# schematic.net
KiCad netlist of a schematic drawn in Altium Designer
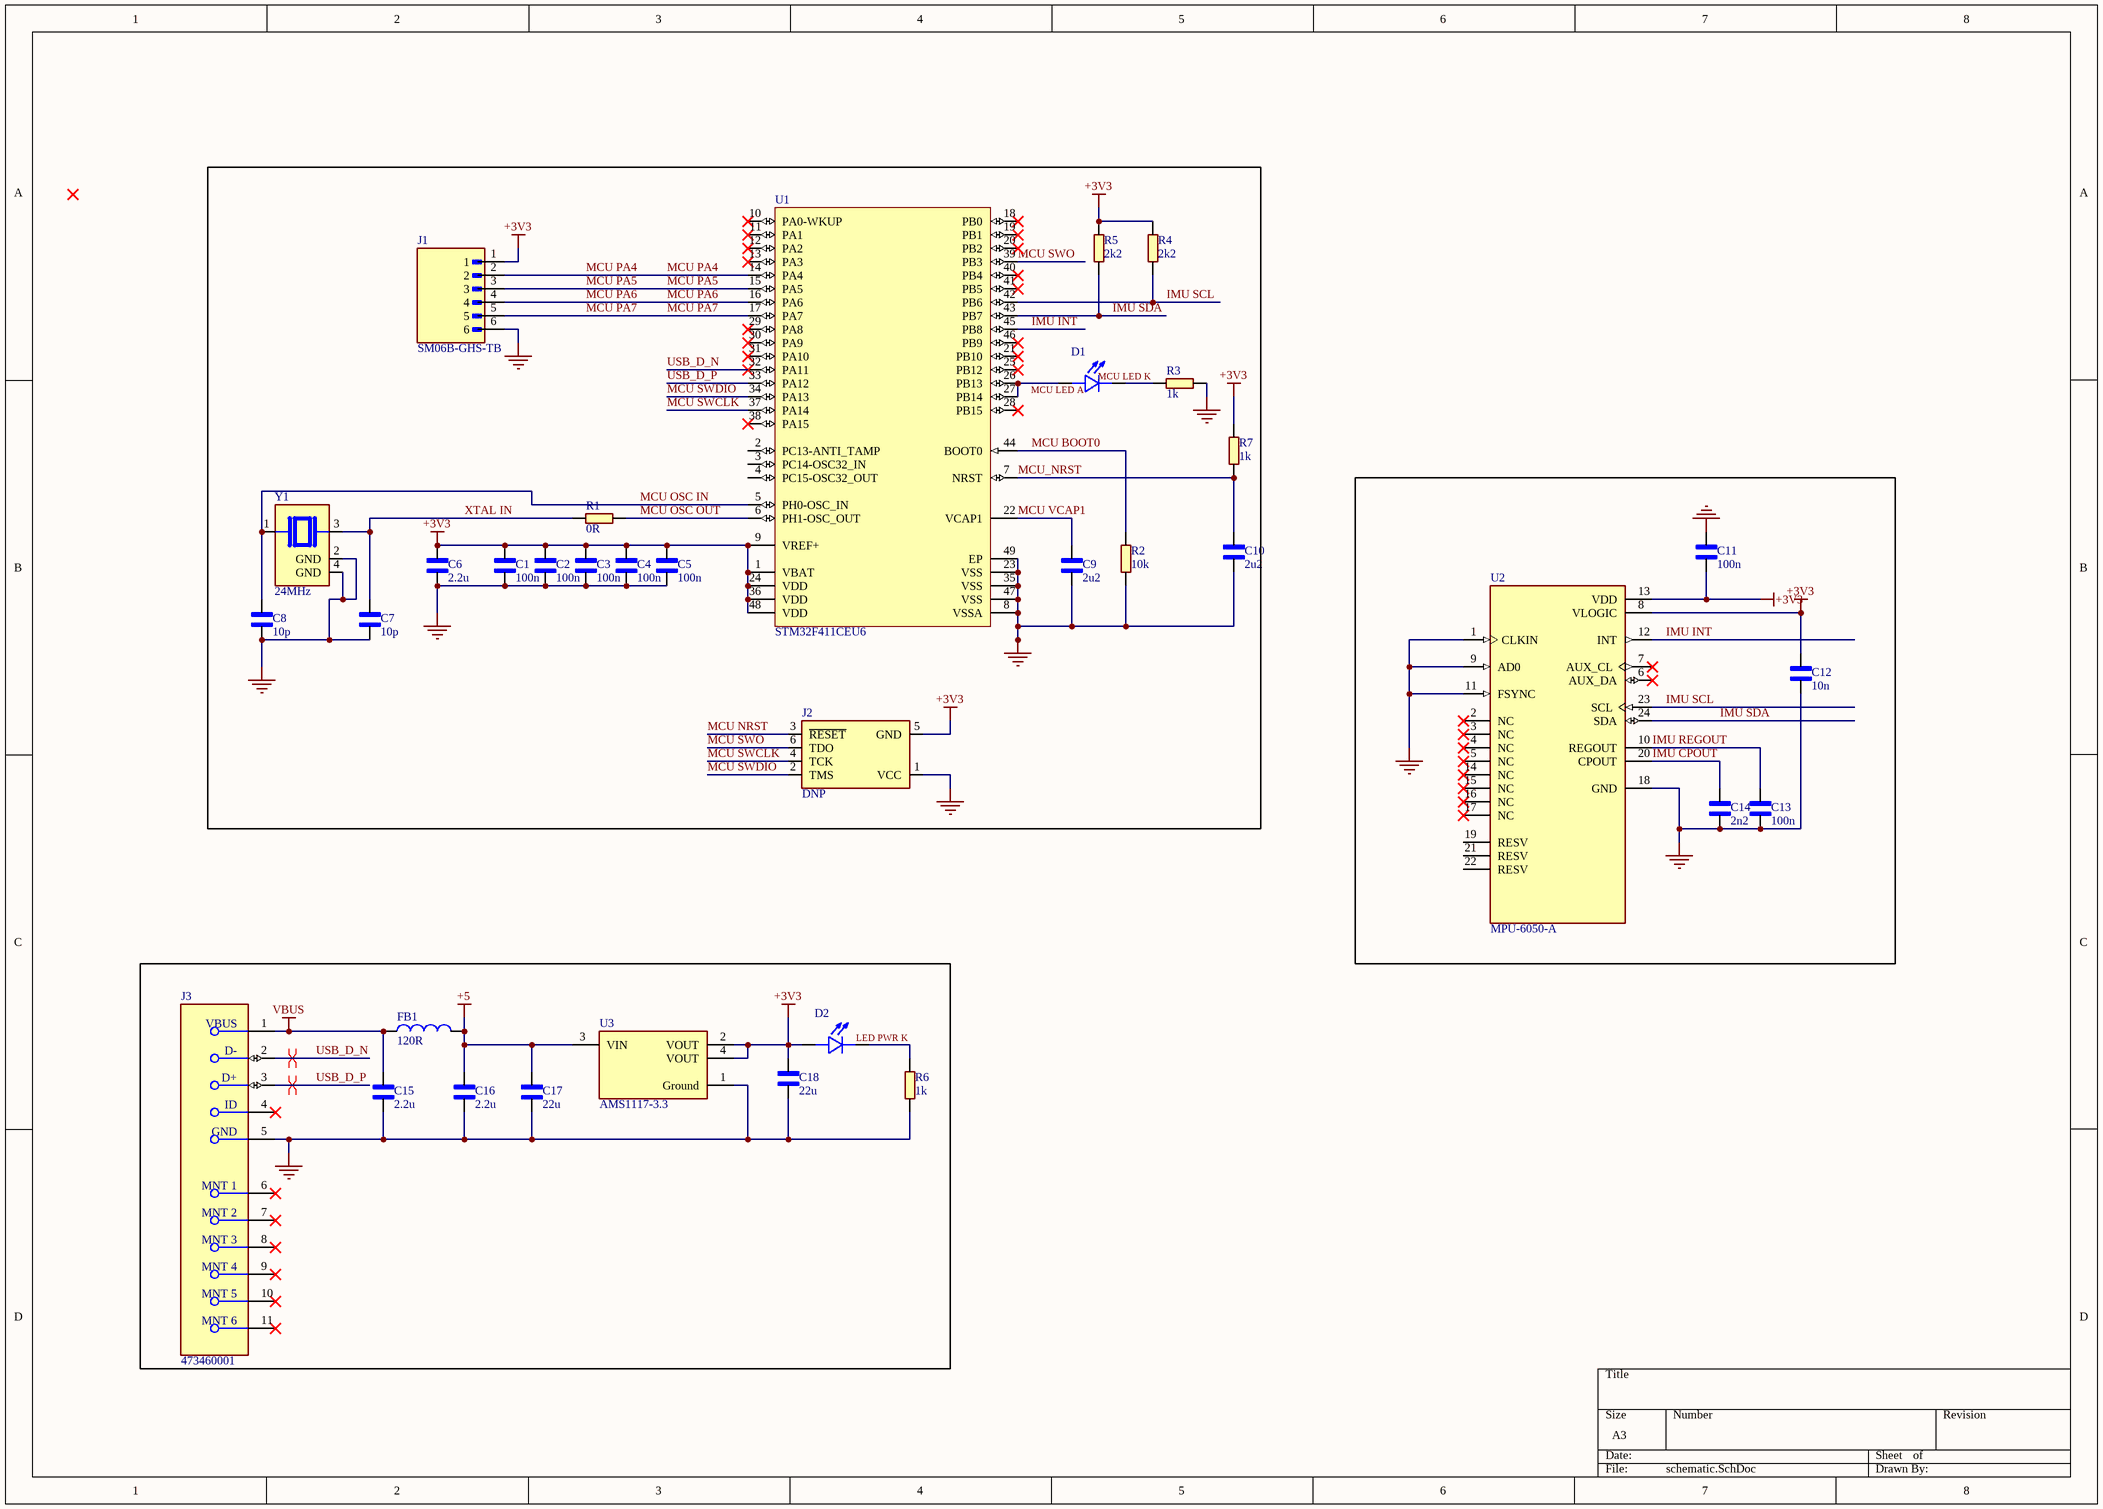
[diagram p0: schematic.SchDoc]

(export (version "E")
  (design (tool "Eeschema 10.0.6"))
  (components
    (comp (ref "C1")
      (value "100n")
      (footprint "CAPC1005X55N")
      (description "10000 pF Â±10% 16V Ceramic Capacitor X7R 0402 (1005 Metric)")
      (fields (field (name "MF") "KEMET") (field (name "MP") "C0402C103K4RAC"))
      (libsource (lib "C0402C103K4RAC") (part "C0402C103K4RAC"))
    )
    (comp (ref "C2")
      (value "100n")
      (footprint "CAPC1005X55N")
      (description "10000 pF Â±10% 16V Ceramic Capacitor X7R 0402 (1005 Metric)")
      (fields (field (name "MF") "KEMET") (field (name "MP") "C0402C103K4RAC"))
      (libsource (lib "C0402C103K4RAC") (part "C0402C103K4RAC"))
    )
    (comp (ref "C3")
      (value "100n")
      (footprint "CAPC1005X55N")
      (description "10000 pF Â±10% 16V Ceramic Capacitor X7R 0402 (1005 Metric)")
      (fields (field (name "MF") "KEMET") (field (name "MP") "C0402C103K4RAC"))
      (libsource (lib "C0402C103K4RAC") (part "C0402C103K4RAC"))
    )
    (comp (ref "C4")
      (value "100n")
      (footprint "CAPC1005X55N")
      (description "10000 pF Â±10% 16V Ceramic Capacitor X7R 0402 (1005 Metric)")
      (fields (field (name "MF") "KEMET") (field (name "MP") "C0402C103K4RAC"))
      (libsource (lib "C0402C103K4RAC") (part "C0402C103K4RAC"))
    )
    (comp (ref "C5")
      (value "100n")
      (footprint "CAPC1005X55N")
      (description "10000 pF Â±10% 16V Ceramic Capacitor X7R 0402 (1005 Metric)")
      (fields (field (name "MF") "KEMET") (field (name "MP") "C0402C103K4RAC"))
      (libsource (lib "C0402C103K4RAC") (part "C0402C103K4RAC"))
    )
    (comp (ref "C6")
      (value "2.2u")
      (footprint "CAPC1608X90N")
      (description "0.1 ÂµF Â±5% 16V Ceramic Capacitor X7R 0603 (1608 Metric)")
      (fields (field (name "MF") "KEMET") (field (name "MP") "C0603C104J4RAC"))
      (libsource (lib "C0603C104J4RAC") (part "C0603C104J4RAC"))
    )
    (comp (ref "C7")
      (value "10p")
      (footprint "CAPC1005X55N")
      (description "10000 pF Â±10% 16V Ceramic Capacitor X7R 0402 (1005 Metric)")
      (fields (field (name "MF") "KEMET") (field (name "MP") "C0402C103K4RAC"))
      (libsource (lib "C0402C103K4RAC") (part "C0402C103K4RAC"))
    )
    (comp (ref "C8")
      (value "10p")
      (footprint "CAPC1005X55N")
      (description "10000 pF Â±10% 16V Ceramic Capacitor X7R 0402 (1005 Metric)")
      (fields (field (name "MF") "KEMET") (field (name "MP") "C0402C103K4RAC"))
      (libsource (lib "C0402C103K4RAC") (part "C0402C103K4RAC"))
    )
    (comp (ref "C9")
      (value "2u2")
      (footprint "CAPC1608X90N")
      (description "0.1 ÂµF Â±5% 16V Ceramic Capacitor X7R 0603 (1608 Metric)")
      (fields (field (name "MF") "KEMET") (field (name "MP") "C0603C104J4RAC"))
      (libsource (lib "C0603C104J4RAC") (part "C0603C104J4RAC"))
    )
    (comp (ref "C10")
      (value "2u2")
      (footprint "CAPC1005X55N")
      (description "10000 pF Â±10% 16V Ceramic Capacitor X7R 0402 (1005 Metric)")
      (fields (field (name "MF") "KEMET") (field (name "MP") "C0402C103K4RAC"))
      (libsource (lib "C0402C103K4RAC") (part "C0402C103K4RAC"))
    )
    (comp (ref "C11")
      (value "100n")
      (footprint "CAPC1005X55N")
      (description "10000 pF Â±10% 16V Ceramic Capacitor X7R 0402 (1005 Metric)")
      (fields (field (name "MF") "KEMET") (field (name "MP") "C0402C103K4RAC"))
      (libsource (lib "C0402C103K4RAC") (part "C0402C103K4RAC"))
    )
    (comp (ref "C12")
      (value "10n")
      (footprint "CAPC1005X55N")
      (description "10000 pF Â±10% 16V Ceramic Capacitor X7R 0402 (1005 Metric)")
      (fields (field (name "MF") "KEMET") (field (name "MP") "C0402C103K4RAC"))
      (libsource (lib "C0402C103K4RAC") (part "C0402C103K4RAC"))
    )
    (comp (ref "C13")
      (value "100n")
      (footprint "CAPC1005X55N")
      (description "10000 pF Â±10% 16V Ceramic Capacitor X7R 0402 (1005 Metric)")
      (fields (field (name "MF") "KEMET") (field (name "MP") "C0402C103K4RAC"))
      (libsource (lib "C0402C103K4RAC") (part "C0402C103K4RAC"))
    )
    (comp (ref "C14")
      (value "2n2")
      (footprint "CAPC1005X55N")
      (description "10000 pF Â±10% 16V Ceramic Capacitor X7R 0402 (1005 Metric)")
      (fields (field (name "MF") "KEMET") (field (name "MP") "C0402C103K4RAC"))
      (libsource (lib "C0402C103K4RAC") (part "C0402C103K4RAC"))
    )
    (comp (ref "C15")
      (value "2.2u")
      (footprint "CAPC1608X90N")
      (description "0.1 ÂµF Â±5% 16V Ceramic Capacitor X7R 0603 (1608 Metric)")
      (fields (field (name "MF") "KEMET") (field (name "MP") "C0603C104J4RAC"))
      (libsource (lib "C0603C104J4RAC") (part "C0603C104J4RAC"))
    )
    (comp (ref "C16")
      (value "2.2u")
      (footprint "CAPC1608X90N")
      (description "0.1 ÂµF Â±5% 16V Ceramic Capacitor X7R 0603 (1608 Metric)")
      (fields (field (name "MF") "KEMET") (field (name "MP") "C0603C104J4RAC"))
      (libsource (lib "C0603C104J4RAC") (part "C0603C104J4RAC"))
    )
    (comp (ref "C17")
      (value "22u")
      (footprint "CAPC1608X90N")
      (description "0.1 ÂµF Â±5% 16V Ceramic Capacitor X7R 0603 (1608 Metric)")
      (fields (field (name "MF") "KEMET") (field (name "MP") "C0603C104J4RAC"))
      (libsource (lib "C0603C104J4RAC") (part "C0603C104J4RAC"))
    )
    (comp (ref "C18")
      (value "22u")
      (footprint "CAPC1608X90N")
      (description "0.1 ÂµF Â±5% 16V Ceramic Capacitor X7R 0603 (1608 Metric)")
      (fields (field (name "MF") "KEMET") (field (name "MP") "C0603C104J4RAC"))
      (libsource (lib "C0603C104J4RAC") (part "C0603C104J4RAC"))
    )
    (comp (ref "D1")
      (value "APHHS1005LSECK/J3-PF")
      (footprint "LED_APHHS1005LSECK/J3-PF")
      (description "Red 625nm LED Indication - Discrete 1.8V 0402 (1005 Metric)")
      (fields (field (name "MF") "Kingbright"))
      (libsource (lib "APHHS1005LSECK_J3-PF") (part "APHHS1005LSECK/J3-PF"))
    )
    (comp (ref "D2")
      (value "APHHS1005LCGCK")
      (footprint "LED_APHHS1005LCGCK")
      (description "Green 570nm LED Indication - Discrete 1.9V 0402 (1005 Metric)")
      (fields (field (name "MF") "Kingbright"))
      (libsource (lib "APHHS1005LCGCK") (part "APHHS1005LCGCK"))
    )
    (comp (ref "FB1")
      (value "120R")
      (footprint "WE-PF_1280")
      (description "FERRITE BEAD 185 OHM 2SMD 1LN")
      (fields (field (name "MF") "WÃ¼rth Elektronik") (field (name "MP") "7427929115"))
      (libsource (lib "WE-PF_1280") (part "WE-PF_1280"))
    )
    (comp (ref "J1")
      (value "SM06B-GHS-TB")
      (footprint "JST_SM06B-GHS-TB")
      (description "Connector Header Surface Mount, Right Angle 6 position 0.049 (1.25mm)")
      (fields (field (name "MF") "JST Sales"))
      (libsource (lib "SM06B-GHS-TB") (part "SM06B-GHS-TB"))
    )
    (comp (ref "J2")
      (value "DNP")
      (footprint "TC2030-IDC-NL")
      (description "CortexÂ® Plug-Of-Nailsâ„¢ Adapter Cable")
      (fields (field (name "MP") "TC2030-CTX") (field (name "MF") "Tag-Connect LLC"))
      (libsource (lib "TC2030-CTX") (part "TC2030-CTX"))
    )
    (comp (ref "J3")
      (value "473460001")
      (footprint "FP-473460001-MFG")
      (description "CONN RCPT USB2.0 MICRO B SMD R/A")
      (fields
        (field (name "OCTOPART") "https://octopart.com/47346-0001-molex-7164928")
        (field (name "MANUFACTURER") "Molex")
      )
      (libsource (lib "Altium Content Vault") (part "53ae1f1d9b557310b43ca686e5bb76a"))
    )
    (comp (ref "R1")
      (value "0R")
      (footprint "0402")
      (description "Reducer,NEMA 1,4 X 2 1/2 ¦ Wiegmann R0402")
      (fields (field (name "MF") "Wiegmann") (field (name "MP") "R0402"))
      (libsource (lib "") (part "R0402_1"))
    )
    (comp (ref "R2")
      (value "10k")
      (footprint "0402")
      (description "Reducer,NEMA 1,4 X 2 1/2 ¦ Wiegmann R0402")
      (fields (field (name "MF") "Wiegmann") (field (name "MP") "R0402"))
      (libsource (lib "R0402") (part "R0402"))
    )
    (comp (ref "R3")
      (value "1k")
      (footprint "0402")
      (description "Reducer,NEMA 1,4 X 2 1/2 ¦ Wiegmann R0402")
      (fields (field (name "MF") "Wiegmann") (field (name "MP") "R0402"))
      (libsource (lib "") (part "R0402_3"))
    )
    (comp (ref "R4")
      (value "2k2")
      (footprint "0402")
      (description "Reducer,NEMA 1,4 X 2 1/2 ¦ Wiegmann R0402")
      (fields (field (name "MF") "Wiegmann") (field (name "MP") "R0402"))
      (libsource (lib "R0402") (part "R0402"))
    )
    (comp (ref "R5")
      (value "2k2")
      (footprint "0402")
      (description "Reducer,NEMA 1,4 X 2 1/2 ¦ Wiegmann R0402")
      (fields (field (name "MF") "Wiegmann") (field (name "MP") "R0402"))
      (libsource (lib "R0402") (part "R0402"))
    )
    (comp (ref "R6")
      (value "1k")
      (footprint "0402")
      (description "Reducer,NEMA 1,4 X 2 1/2 ¦ Wiegmann R0402")
      (fields (field (name "MF") "Wiegmann") (field (name "MP") "R0402"))
      (libsource (lib "R0402") (part "R0402"))
    )
    (comp (ref "R7")
      (value "1k")
      (footprint "0402")
      (description "Reducer,NEMA 1,4 X 2 1/2 ¦ Wiegmann R0402")
      (fields (field (name "MF") "Wiegmann") (field (name "MP") "R0402"))
      (libsource (lib "") (part "R0402_2"))
    )
    (comp (ref "U1")
      (value "STM32F411CEU6")
      (footprint "STM-UFQFPN48_L")
      (libsource (lib "Altium Content Vault") (part "MC-ARM-STM32F411-UFQFPN48"))
    )
    (comp (ref "U2")
      (value "MPU-6050-A")
      (footprint "QFN50P400X400X95-24N")
      (fields (field (name "MF") "TDK InvenSense"))
      (libsource (lib "MPU-6050-A") (part "MPU-6050-A"))
    )
    (comp (ref "U3")
      (value "AMS1117-3.3")
      (footprint "FP-AMS1117-IPC_C")
      (description "LDO Voltage Regulators 1A, 3.3V")
      (fields
        (field (name "OCTOPART") "https://octopart.com/ams1117-3.3-advanced+monolithic+systems-25899300")
        (field (name "MANUFACTURER") "Advanced Monolithic Systems")
      )
      (libsource (lib "Altium Content Vault") (part "8bdbb5f8e77002000e30dd2845d0354"))
    )
    (comp (ref "Y1")
      (value "24MHz")
      (footprint "XTAL_TSX-3225_24.0000MF15V-C0")
      (description "24 MHz Â±10ppm Crystal 18pF 40 Ohms 4-SMD, No Lead")
      (fields (field (name "MF") "EPSON") (field (name "DIGI-KEY_PART_NUMBER") "SER4209TR-ND"))
      (libsource (lib "TSX-3225_24.0000MF15V-C0") (part "TSX-3225_24.0000MF15V-C0"))
    )
  )
  (nets
    (net (code "1") (name "+3V3") (class "Default")
      (node (ref "C1") (pin "2") (pinfunction "2_2") (pintype "passive"))
      (node (ref "C11") (pin "1") (pinfunction "1_1") (pintype "passive"))
      (node (ref "C12") (pin "2") (pinfunction "2_2") (pintype "passive"))
      (node (ref "C18") (pin "2") (pinfunction "2_2") (pintype "passive"))
      (node (ref "C2") (pin "2") (pinfunction "2_2") (pintype "passive"))
      (node (ref "C3") (pin "2") (pinfunction "2_2") (pintype "passive"))
      (node (ref "C4") (pin "2") (pinfunction "2_2") (pintype "passive"))
      (node (ref "C5") (pin "2") (pinfunction "2_2") (pintype "passive"))
      (node (ref "C6") (pin "2") (pinfunction "2_2") (pintype "passive"))
      (node (ref "D2") (pin "2") (pinfunction "A_2") (pintype "passive"))
      (node (ref "J1") (pin "1") (pinfunction "1_1") (pintype "passive"))
      (node (ref "J2") (pin "5") (pinfunction "GND_5") (pintype "bidirectional"))
      (node (ref "R4") (pin "2") (pinfunction "2_2") (pintype "passive"))
      (node (ref "R5") (pin "2") (pinfunction "2_2") (pintype "passive"))
      (node (ref "R7") (pin "1") (pinfunction "1_1") (pintype "passive"))
      (node (ref "U1") (pin "1") (pinfunction "VBAT_1") (pintype "power_in"))
      (node (ref "U1") (pin "24") (pinfunction "VDD_24") (pintype "power_in"))
      (node (ref "U1") (pin "36") (pinfunction "VDD_36") (pintype "power_in"))
      (node (ref "U1") (pin "48") (pinfunction "VDD_48") (pintype "power_in"))
      (node (ref "U1") (pin "9") (pinfunction "VREF+_9") (pintype "power_in"))
      (node (ref "U2") (pin "13") (pinfunction "VDD_13") (pintype "power_in"))
      (node (ref "U2") (pin "8") (pinfunction "VLOGIC_8") (pintype "power_in"))
      (node (ref "U3") (pin "2") (pinfunction "VOUT_2") (pintype "passive"))
      (node (ref "U3") (pin "4") (pinfunction "VOUT_4") (pintype "passive"))
    )
    (net (code "2") (name "+5") (class "Default")
      (node (ref "C16") (pin "2") (pinfunction "2_2") (pintype "passive"))
      (node (ref "C17") (pin "2") (pinfunction "2_2") (pintype "passive"))
      (node (ref "FB1") (pin "2") (pinfunction "2_2") (pintype "passive"))
      (node (ref "U3") (pin "3") (pinfunction "VIN_3") (pintype "power_in"))
    )
    (net (code "3") (name "/IMU CPOUT") (class "Default")
      (node (ref "C14") (pin "2") (pinfunction "2_2") (pintype "passive"))
      (node (ref "U2") (pin "20") (pinfunction "CPOUT_20") (pintype "passive"))
    )
    (net (code "4") (name "/IMU INT") (class "Default")
      (node (ref "U1") (pin "45") (pinfunction "PB8_45") (pintype "bidirectional"))
      (node (ref "U2") (pin "12") (pinfunction "INT_12") (pintype "output"))
    )
    (net (code "5") (name "/IMU REGOUT") (class "Default")
      (node (ref "C13") (pin "2") (pinfunction "2_2") (pintype "passive"))
      (node (ref "U2") (pin "10") (pinfunction "REGOUT_10") (pintype "passive"))
    )
    (net (code "6") (name "/IMU SCL") (class "Default")
      (node (ref "R4") (pin "1") (pinfunction "1_1") (pintype "passive"))
      (node (ref "U1") (pin "42") (pinfunction "PB6_42") (pintype "bidirectional"))
      (node (ref "U2") (pin "23") (pinfunction "SCL_23") (pintype "input"))
    )
    (net (code "7") (name "/IMU SDA") (class "Default")
      (node (ref "R5") (pin "1") (pinfunction "1_1") (pintype "passive"))
      (node (ref "U1") (pin "43") (pinfunction "PB7_43") (pintype "bidirectional"))
      (node (ref "U2") (pin "24") (pinfunction "SDA_24") (pintype "bidirectional"))
    )
    (net (code "9") (name "/MCU BOOT0") (class "Default")
      (node (ref "R2") (pin "2") (pinfunction "2_2") (pintype "passive"))
      (node (ref "U1") (pin "44") (pinfunction "BOOT0_44") (pintype "input"))
    )
    (net (code "11") (name "/MCU LED K") (class "Default")
      (node (ref "D1") (pin "1") (pinfunction "C_1") (pintype "passive"))
      (node (ref "R3") (pin "2") (pinfunction "2_2") (pintype "passive"))
    )
    (net (code "12") (name "/MCU NRST") (class "Default")
      (node (ref "J2") (pin "3") (pinfunction "~{RESET}_3") (pintype "bidirectional"))
    )
    (net (code "13") (name "/MCU OSC IN") (class "Default")
      (node (ref "C8") (pin "2") (pinfunction "2_2") (pintype "passive"))
      (node (ref "U1") (pin "5") (pinfunction "PH0-OSC_IN_5") (pintype "bidirectional"))
      (node (ref "Y1") (pin "1") (pinfunction "1_1") (pintype "passive"))
    )
    (net (code "14") (name "/MCU OSC OUT") (class "Default")
      (node (ref "R1") (pin "2") (pinfunction "2_2") (pintype "passive"))
      (node (ref "U1") (pin "6") (pinfunction "PH1-OSC_OUT_6") (pintype "bidirectional"))
    )
    (net (code "15") (name "/MCU PA4") (class "Default")
      (node (ref "J1") (pin "2") (pinfunction "2_2") (pintype "passive"))
      (node (ref "U1") (pin "14") (pinfunction "PA4_14") (pintype "bidirectional"))
    )
    (net (code "16") (name "/MCU PA5") (class "Default")
      (node (ref "J1") (pin "3") (pinfunction "3_3") (pintype "passive"))
      (node (ref "U1") (pin "15") (pinfunction "PA5_15") (pintype "bidirectional"))
    )
    (net (code "17") (name "/MCU PA6") (class "Default")
      (node (ref "J1") (pin "4") (pinfunction "4_4") (pintype "passive"))
      (node (ref "U1") (pin "16") (pinfunction "PA6_16") (pintype "bidirectional"))
    )
    (net (code "18") (name "/MCU PA7") (class "Default")
      (node (ref "J1") (pin "5") (pinfunction "5_5") (pintype "passive"))
      (node (ref "U1") (pin "17") (pinfunction "PA7_17") (pintype "bidirectional"))
    )
    (net (code "19") (name "/MCU SWCLK") (class "Default")
      (node (ref "J2") (pin "4") (pinfunction "TCK_4") (pintype "bidirectional"))
      (node (ref "U1") (pin "37") (pinfunction "PA14_37") (pintype "bidirectional"))
    )
    (net (code "20") (name "/MCU SWDIO") (class "Default")
      (node (ref "J2") (pin "2") (pinfunction "TMS_2") (pintype "bidirectional"))
      (node (ref "U1") (pin "34") (pinfunction "PA13_34") (pintype "bidirectional"))
    )
    (net (code "21") (name "/MCU SWO") (class "Default")
      (node (ref "J2") (pin "6") (pinfunction "TDO_6") (pintype "bidirectional"))
      (node (ref "U1") (pin "39") (pinfunction "PB3_39") (pintype "bidirectional"))
    )
    (net (code "22") (name "/MCU VCAP1") (class "Default")
      (node (ref "C9") (pin "2") (pinfunction "2_2") (pintype "passive"))
      (node (ref "U1") (pin "22") (pinfunction "VCAP1_22") (pintype "passive"))
    )
    (net (code "23") (name "/MCU_NRST") (class "Default")
      (node (ref "C10") (pin "2") (pinfunction "2_2") (pintype "passive"))
      (node (ref "R7") (pin "2") (pinfunction "2_2") (pintype "passive"))
      (node (ref "U1") (pin "7") (pinfunction "NRST_7") (pintype "bidirectional"))
    )
    (net (code "24") (name "/USB_D_N") (class "Default")
      (node (ref "J3") (pin "2") (pinfunction "D-_2") (pintype "bidirectional"))
      (node (ref "U1") (pin "32") (pinfunction "PA11_32") (pintype "bidirectional"))
    )
    (net (code "25") (name "/USB_D_P") (class "Default")
      (node (ref "J3") (pin "3") (pinfunction "D+_3") (pintype "bidirectional"))
      (node (ref "U1") (pin "33") (pinfunction "PA12_33") (pintype "bidirectional"))
    )
    (net (code "26") (name "/XTAL IN") (class "Default")
      (node (ref "C7") (pin "2") (pinfunction "2_2") (pintype "passive"))
      (node (ref "R1") (pin "1") (pinfunction "1_1") (pintype "passive"))
      (node (ref "Y1") (pin "3") (pinfunction "2_3") (pintype "passive"))
    )
    (net (code "27") (name "GND") (class "Default")
      (node (ref "C1") (pin "1") (pinfunction "1_1") (pintype "passive"))
      (node (ref "C10") (pin "1") (pinfunction "1_1") (pintype "passive"))
      (node (ref "C11") (pin "2") (pinfunction "2_2") (pintype "passive"))
      (node (ref "C12") (pin "1") (pinfunction "1_1") (pintype "passive"))
      (node (ref "C13") (pin "1") (pinfunction "1_1") (pintype "passive"))
      (node (ref "C14") (pin "1") (pinfunction "1_1") (pintype "passive"))
      (node (ref "C15") (pin "1") (pinfunction "1_1") (pintype "passive"))
      (node (ref "C16") (pin "1") (pinfunction "1_1") (pintype "passive"))
      (node (ref "C17") (pin "1") (pinfunction "1_1") (pintype "passive"))
      (node (ref "C18") (pin "1") (pinfunction "1_1") (pintype "passive"))
      (node (ref "C2") (pin "1") (pinfunction "1_1") (pintype "passive"))
      (node (ref "C3") (pin "1") (pinfunction "1_1") (pintype "passive"))
      (node (ref "C4") (pin "1") (pinfunction "1_1") (pintype "passive"))
      (node (ref "C5") (pin "1") (pinfunction "1_1") (pintype "passive"))
      (node (ref "C6") (pin "1") (pinfunction "1_1") (pintype "passive"))
      (node (ref "C7") (pin "1") (pinfunction "1_1") (pintype "passive"))
      (node (ref "C8") (pin "1") (pinfunction "1_1") (pintype "passive"))
      (node (ref "C9") (pin "1") (pinfunction "1_1") (pintype "passive"))
      (node (ref "J1") (pin "6") (pinfunction "6_6") (pintype "passive"))
      (node (ref "J2") (pin "1") (pinfunction "VCC_1") (pintype "bidirectional"))
      (node (ref "J3") (pin "5") (pinfunction "GND_5") (pintype "power_in"))
      (node (ref "R2") (pin "1") (pinfunction "1_1") (pintype "passive"))
      (node (ref "R3") (pin "1") (pinfunction "1_1") (pintype "passive"))
      (node (ref "R6") (pin "1") (pinfunction "1_1") (pintype "passive"))
      (node (ref "U1") (pin "23") (pinfunction "VSS_23") (pintype "power_in"))
      (node (ref "U1") (pin "35") (pinfunction "VSS_35") (pintype "power_in"))
      (node (ref "U1") (pin "47") (pinfunction "VSS_47") (pintype "power_in"))
      (node (ref "U1") (pin "49") (pinfunction "EP_49") (pintype "power_in"))
      (node (ref "U1") (pin "8") (pinfunction "VSSA_8") (pintype "power_in"))
      (node (ref "U2") (pin "1") (pinfunction "CLKIN_1") (pintype "input"))
      (node (ref "U2") (pin "11") (pinfunction "FSYNC_11") (pintype "input"))
      (node (ref "U2") (pin "18") (pinfunction "GND_18") (pintype "power_in"))
      (node (ref "U2") (pin "9") (pinfunction "AD0_9") (pintype "input"))
      (node (ref "U3") (pin "1") (pinfunction "Ground_1") (pintype "power_in"))
      (node (ref "Y1") (pin "2") (pinfunction "GND_2") (pintype "power_in"))
      (node (ref "Y1") (pin "4") (pinfunction "GND_4") (pintype "power_in"))
    )
    (net (code "28") (name "Net-(D1-A)") (class "Default")
      (node (ref "D1") (pin "2") (pinfunction "A_2") (pintype "passive"))
      (node (ref "U1") (pin "26") (pinfunction "PB13_26") (pintype "bidirectional"))
      (node (ref "U1") (pin "27") (pinfunction "PB14_27") (pintype "bidirectional"))
    )
    (net (code "29") (name "Net-(D2-C)") (class "Default")
      (node (ref "D2") (pin "1") (pinfunction "C_1") (pintype "passive"))
      (node (ref "R6") (pin "2") (pinfunction "2_2") (pintype "passive"))
    )
    (net (code "30") (name "VBUS") (class "Default")
      (node (ref "C15") (pin "2") (pinfunction "2_2") (pintype "passive"))
      (node (ref "FB1") (pin "1") (pinfunction "1_1") (pintype "passive"))
      (node (ref "J3") (pin "1") (pinfunction "VBUS_1") (pintype "power_in"))
    )
    (net (code "31") (name "unconnected-(J3-ID-Pad4)") (class "Default")
      (node (ref "J3") (pin "4") (pinfunction "ID_4") (pintype "passive+no_connect"))
    )
    (net (code "32") (name "unconnected-(J3-MNT_1-Pad6)") (class "Default")
      (node (ref "J3") (pin "6") (pinfunction "MNT_1_6") (pintype "passive+no_connect"))
    )
    (net (code "33") (name "unconnected-(J3-MNT_2-Pad7)") (class "Default")
      (node (ref "J3") (pin "7") (pinfunction "MNT_2_7") (pintype "passive+no_connect"))
    )
    (net (code "34") (name "unconnected-(J3-MNT_3-Pad8)") (class "Default")
      (node (ref "J3") (pin "8") (pinfunction "MNT_3_8") (pintype "passive+no_connect"))
    )
    (net (code "35") (name "unconnected-(J3-MNT_4-Pad9)") (class "Default")
      (node (ref "J3") (pin "9") (pinfunction "MNT_4_9") (pintype "passive+no_connect"))
    )
    (net (code "36") (name "unconnected-(J3-MNT_5-Pad10)") (class "Default")
      (node (ref "J3") (pin "10") (pinfunction "MNT_5_10") (pintype "passive+no_connect"))
    )
    (net (code "37") (name "unconnected-(J3-MNT_6-Pad11)") (class "Default")
      (node (ref "J3") (pin "11") (pinfunction "MNT_6_11") (pintype "passive+no_connect"))
    )
    (net (code "38") (name "unconnected-(U1-PA0-WKUP-Pad10)") (class "Default")
      (node (ref "U1") (pin "10") (pinfunction "PA0-WKUP_10") (pintype "bidirectional+no_connect"))
    )
    (net (code "39") (name "unconnected-(U1-PA1-Pad11)") (class "Default")
      (node (ref "U1") (pin "11") (pinfunction "PA1_11") (pintype "bidirectional+no_connect"))
    )
    (net (code "40") (name "unconnected-(U1-PA2-Pad12)") (class "Default")
      (node (ref "U1") (pin "12") (pinfunction "PA2_12") (pintype "bidirectional+no_connect"))
    )
    (net (code "41") (name "unconnected-(U1-PA3-Pad13)") (class "Default")
      (node (ref "U1") (pin "13") (pinfunction "PA3_13") (pintype "bidirectional+no_connect"))
    )
    (net (code "42") (name "unconnected-(U1-PA8-Pad29)") (class "Default")
      (node (ref "U1") (pin "29") (pinfunction "PA8_29") (pintype "bidirectional+no_connect"))
    )
    (net (code "43") (name "unconnected-(U1-PA9-Pad30)") (class "Default")
      (node (ref "U1") (pin "30") (pinfunction "PA9_30") (pintype "bidirectional+no_connect"))
    )
    (net (code "44") (name "unconnected-(U1-PA10-Pad31)") (class "Default")
      (node (ref "U1") (pin "31") (pinfunction "PA10_31") (pintype "bidirectional+no_connect"))
    )
    (net (code "45") (name "unconnected-(U1-PA15-Pad38)") (class "Default")
      (node (ref "U1") (pin "38") (pinfunction "PA15_38") (pintype "bidirectional+no_connect"))
    )
    (net (code "46") (name "unconnected-(U1-PB0-Pad18)") (class "Default")
      (node (ref "U1") (pin "18") (pinfunction "PB0_18") (pintype "bidirectional+no_connect"))
    )
    (net (code "47") (name "unconnected-(U1-PB1-Pad19)") (class "Default")
      (node (ref "U1") (pin "19") (pinfunction "PB1_19") (pintype "bidirectional+no_connect"))
    )
    (net (code "48") (name "unconnected-(U1-PB2-Pad20)") (class "Default")
      (node (ref "U1") (pin "20") (pinfunction "PB2_20") (pintype "bidirectional+no_connect"))
    )
    (net (code "49") (name "unconnected-(U1-PB4-Pad40)") (class "Default")
      (node (ref "U1") (pin "40") (pinfunction "PB4_40") (pintype "bidirectional+no_connect"))
    )
    (net (code "50") (name "unconnected-(U1-PB5-Pad41)") (class "Default")
      (node (ref "U1") (pin "41") (pinfunction "PB5_41") (pintype "bidirectional+no_connect"))
    )
    (net (code "51") (name "unconnected-(U1-PB9-Pad46)") (class "Default")
      (node (ref "U1") (pin "46") (pinfunction "PB9_46") (pintype "bidirectional+no_connect"))
    )
    (net (code "52") (name "unconnected-(U1-PB10-Pad21)") (class "Default")
      (node (ref "U1") (pin "21") (pinfunction "PB10_21") (pintype "bidirectional+no_connect"))
    )
    (net (code "53") (name "unconnected-(U1-PB12-Pad25)") (class "Default")
      (node (ref "U1") (pin "25") (pinfunction "PB12_25") (pintype "bidirectional+no_connect"))
    )
    (net (code "54") (name "unconnected-(U1-PB15-Pad28)") (class "Default")
      (node (ref "U1") (pin "28") (pinfunction "PB15_28") (pintype "bidirectional+no_connect"))
    )
    (net (code "55") (name "unconnected-(U1-PC13-ANTI_TAMP-Pad2)") (class "Default")
      (node (ref "U1") (pin "2") (pinfunction "PC13-ANTI_TAMP_2") (pintype "bidirectional"))
    )
    (net (code "56") (name "unconnected-(U1-PC14-OSC32_IN-Pad3)") (class "Default")
      (node (ref "U1") (pin "3") (pinfunction "PC14-OSC32_IN_3") (pintype "bidirectional"))
    )
    (net (code "57") (name "unconnected-(U1-PC15-OSC32_OUT-Pad4)") (class "Default")
      (node (ref "U1") (pin "4") (pinfunction "PC15-OSC32_OUT_4") (pintype "bidirectional"))
    )
    (net (code "58") (name "unconnected-(U2-AUX_CL-Pad7)") (class "Default")
      (node (ref "U2") (pin "7") (pinfunction "AUX_CL_7") (pintype "output+no_connect"))
    )
    (net (code "59") (name "unconnected-(U2-AUX_DA-Pad6)") (class "Default")
      (node (ref "U2") (pin "6") (pinfunction "AUX_DA_6") (pintype "bidirectional+no_connect"))
    )
    (net (code "60") (name "unconnected-(U2-NC-Pad2)") (class "Default")
      (node (ref "U2") (pin "2") (pinfunction "NC_2") (pintype "passive+no_connect"))
    )
    (net (code "61") (name "unconnected-(U2-NC-Pad3)") (class "Default")
      (node (ref "U2") (pin "3") (pinfunction "NC_3") (pintype "passive+no_connect"))
    )
    (net (code "62") (name "unconnected-(U2-NC-Pad4)") (class "Default")
      (node (ref "U2") (pin "4") (pinfunction "NC_4") (pintype "passive+no_connect"))
    )
    (net (code "63") (name "unconnected-(U2-NC-Pad5)") (class "Default")
      (node (ref "U2") (pin "5") (pinfunction "NC_5") (pintype "passive+no_connect"))
    )
    (net (code "64") (name "unconnected-(U2-NC-Pad14)") (class "Default")
      (node (ref "U2") (pin "14") (pinfunction "NC_14") (pintype "passive+no_connect"))
    )
    (net (code "65") (name "unconnected-(U2-NC-Pad15)") (class "Default")
      (node (ref "U2") (pin "15") (pinfunction "NC_15") (pintype "passive+no_connect"))
    )
    (net (code "66") (name "unconnected-(U2-NC-Pad16)") (class "Default")
      (node (ref "U2") (pin "16") (pinfunction "NC_16") (pintype "passive+no_connect"))
    )
    (net (code "67") (name "unconnected-(U2-NC-Pad17)") (class "Default")
      (node (ref "U2") (pin "17") (pinfunction "NC_17") (pintype "passive+no_connect"))
    )
    (net (code "68") (name "unconnected-(U2-RESV-Pad19)") (class "Default")
      (node (ref "U2") (pin "19") (pinfunction "RESV_19") (pintype "passive"))
    )
    (net (code "69") (name "unconnected-(U2-RESV-Pad21)") (class "Default")
      (node (ref "U2") (pin "21") (pinfunction "RESV_21") (pintype "passive"))
    )
    (net (code "70") (name "unconnected-(U2-RESV-Pad22)") (class "Default")
      (node (ref "U2") (pin "22") (pinfunction "RESV_22") (pintype "passive"))
    )
  )
)
